# shield-rs422-B.net
KiCad netlist of a schematic drawn in EAGLE
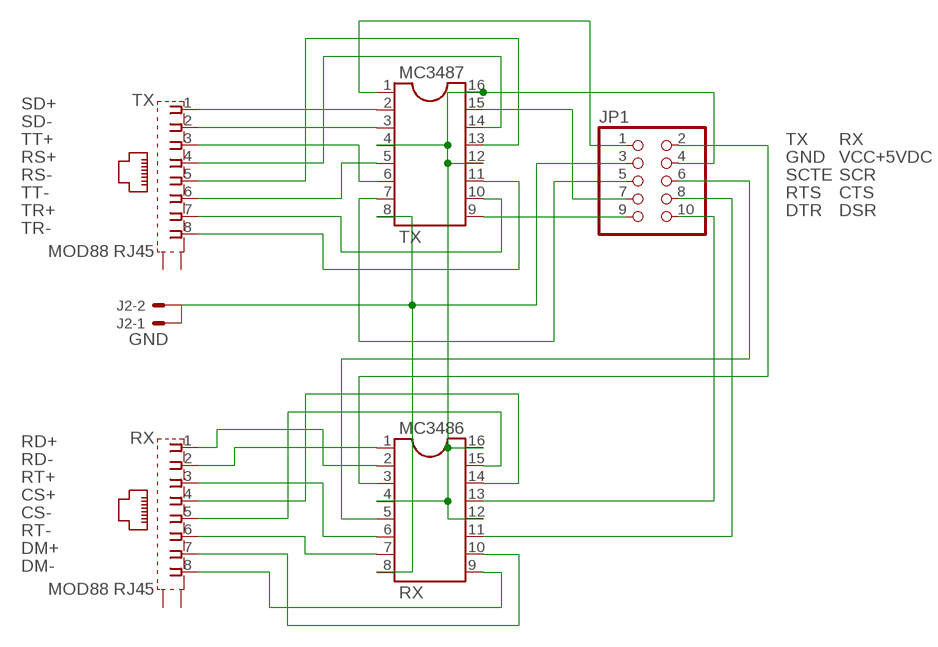
[diagram p0: schematic, sheet 1]

(export (version "E")
  (design (tool "Eeschema 10.0.6"))
  (components
    (comp (ref "J2")
      (value "GND")
      (footprint "eagle-import:7395-02")
      (libsource (lib "eagle-import") (part "22-?-0205-7028"))
    )
    (comp (ref "JP1")
      (value "PINHD-2X5/90")
      (footprint "eagle-import:2X05_90")
      (libsource (lib "eagle-import") (part "PINHD-2X5/90"))
    )
    (comp (ref "MC3486")
      (value "RX")
      (footprint "eagle-import:DIL16")
      (libsource (lib "eagle-import") (part "DIL16"))
    )
    (comp (ref "MC3487")
      (value "TX")
      (footprint "eagle-import:DIL16")
      (libsource (lib "eagle-import") (part "DIL16"))
    )
    (comp (ref "RX")
      (value "MOD88 RJ45")
      (footprint "eagle-import:GLX-S-88M")
      (libsource (lib "eagle-import") (part "GLX-S-88M"))
    )
    (comp (ref "TX")
      (value "MOD88 RJ45")
      (footprint "eagle-import:GLX-S-88M")
      (libsource (lib "eagle-import") (part "GLX-S-88M"))
    )
  )
  (nets
    (net (code "1") (name "/CS+") (class "Default")
      (node (ref "MC3486") (pin "14") (pinfunction "14_14") (pintype "passive"))
      (node (ref "RX") (pin "4") (pinfunction "4_4") (pintype "passive"))
    )
    (net (code "2") (name "/CS-") (class "Default")
      (node (ref "MC3486") (pin "15") (pinfunction "15_15") (pintype "passive"))
      (node (ref "RX") (pin "5") (pinfunction "5_5") (pintype "passive"))
    )
    (net (code "3") (name "/CTS") (class "Default")
      (node (ref "JP1") (pin "8") (pinfunction "8_8") (pintype "passive"))
      (node (ref "MC3486") (pin "11") (pinfunction "11_11") (pintype "passive"))
    )
    (net (code "4") (name "/DM+") (class "Default")
      (node (ref "MC3486") (pin "10") (pinfunction "10_10") (pintype "passive"))
      (node (ref "RX") (pin "7") (pinfunction "7_7") (pintype "passive"))
    )
    (net (code "5") (name "/DM-") (class "Default")
      (node (ref "MC3486") (pin "9") (pinfunction "9_9") (pintype "passive"))
      (node (ref "RX") (pin "8") (pinfunction "8_8") (pintype "passive"))
    )
    (net (code "6") (name "/DSR") (class "Default")
      (node (ref "JP1") (pin "10") (pinfunction "10_10") (pintype "passive"))
      (node (ref "MC3486") (pin "13") (pinfunction "13_13") (pintype "passive"))
    )
    (net (code "7") (name "/DTR") (class "Default")
      (node (ref "JP1") (pin "9") (pinfunction "9_9") (pintype "passive"))
      (node (ref "MC3487") (pin "9") (pinfunction "9_9") (pintype "passive"))
    )
    (net (code "8") (name "/GND") (class "Default")
      (node (ref "J2") (pin "1") (pinfunction "S_1") (pintype "passive"))
      (node (ref "J2") (pin "2") (pinfunction "S_2") (pintype "passive"))
      (node (ref "JP1") (pin "3") (pinfunction "3_3") (pintype "passive"))
      (node (ref "MC3486") (pin "8") (pinfunction "8_8") (pintype "passive"))
      (node (ref "MC3487") (pin "8") (pinfunction "8_8") (pintype "passive"))
    )
    (net (code "9") (name "/RD+") (class "Default")
      (node (ref "MC3486") (pin "2") (pinfunction "2_2") (pintype "passive"))
      (node (ref "RX") (pin "1") (pinfunction "1_1") (pintype "passive"))
    )
    (net (code "10") (name "/RD-") (class "Default")
      (node (ref "MC3486") (pin "1") (pinfunction "1_1") (pintype "passive"))
      (node (ref "RX") (pin "2") (pinfunction "2_2") (pintype "passive"))
    )
    (net (code "11") (name "/RS+") (class "Default")
      (node (ref "MC3487") (pin "14") (pinfunction "14_14") (pintype "passive"))
      (node (ref "TX") (pin "4") (pinfunction "4_4") (pintype "passive"))
    )
    (net (code "12") (name "/RS-") (class "Default")
      (node (ref "MC3487") (pin "13") (pinfunction "13_13") (pintype "passive"))
      (node (ref "TX") (pin "5") (pinfunction "5_5") (pintype "passive"))
    )
    (net (code "13") (name "/RT+") (class "Default")
      (node (ref "MC3486") (pin "6") (pinfunction "6_6") (pintype "passive"))
      (node (ref "RX") (pin "3") (pinfunction "3_3") (pintype "passive"))
    )
    (net (code "14") (name "/RT-") (class "Default")
      (node (ref "MC3486") (pin "7") (pinfunction "7_7") (pintype "passive"))
      (node (ref "RX") (pin "6") (pinfunction "6_6") (pintype "passive"))
    )
    (net (code "15") (name "/RTS") (class "Default")
      (node (ref "JP1") (pin "7") (pinfunction "7_7") (pintype "passive"))
      (node (ref "MC3487") (pin "15") (pinfunction "15_15") (pintype "passive"))
    )
    (net (code "16") (name "/RX") (class "Default")
      (node (ref "JP1") (pin "2") (pinfunction "2_2") (pintype "passive"))
      (node (ref "MC3486") (pin "3") (pinfunction "3_3") (pintype "passive"))
    )
    (net (code "17") (name "/SCR") (class "Default")
      (node (ref "JP1") (pin "6") (pinfunction "6_6") (pintype "passive"))
      (node (ref "MC3486") (pin "5") (pinfunction "5_5") (pintype "passive"))
    )
    (net (code "18") (name "/SCTE") (class "Default")
      (node (ref "JP1") (pin "5") (pinfunction "5_5") (pintype "passive"))
      (node (ref "MC3487") (pin "7") (pinfunction "7_7") (pintype "passive"))
    )
    (net (code "19") (name "/SD+") (class "Default")
      (node (ref "MC3487") (pin "2") (pinfunction "2_2") (pintype "passive"))
      (node (ref "TX") (pin "1") (pinfunction "1_1") (pintype "passive"))
    )
    (net (code "20") (name "/SD-") (class "Default")
      (node (ref "MC3487") (pin "3") (pinfunction "3_3") (pintype "passive"))
      (node (ref "TX") (pin "2") (pinfunction "2_2") (pintype "passive"))
    )
    (net (code "21") (name "/TR+") (class "Default")
      (node (ref "MC3487") (pin "10") (pinfunction "10_10") (pintype "passive"))
      (node (ref "TX") (pin "7") (pinfunction "7_7") (pintype "passive"))
    )
    (net (code "22") (name "/TR-") (class "Default")
      (node (ref "MC3487") (pin "11") (pinfunction "11_11") (pintype "passive"))
      (node (ref "TX") (pin "8") (pinfunction "8_8") (pintype "passive"))
    )
    (net (code "23") (name "/TT+") (class "Default")
      (node (ref "MC3487") (pin "6") (pinfunction "6_6") (pintype "passive"))
      (node (ref "TX") (pin "3") (pinfunction "3_3") (pintype "passive"))
    )
    (net (code "24") (name "/TT-") (class "Default")
      (node (ref "MC3487") (pin "5") (pinfunction "5_5") (pintype "passive"))
      (node (ref "TX") (pin "6") (pinfunction "6_6") (pintype "passive"))
    )
    (net (code "25") (name "/TX") (class "Default")
      (node (ref "JP1") (pin "1") (pinfunction "1_1") (pintype "passive"))
      (node (ref "MC3487") (pin "1") (pinfunction "1_1") (pintype "passive"))
    )
    (net (code "26") (name "/VCC+5VDC") (class "Default")
      (node (ref "JP1") (pin "4") (pinfunction "4_4") (pintype "passive"))
      (node (ref "MC3486") (pin "12") (pinfunction "12_12") (pintype "passive"))
      (node (ref "MC3486") (pin "16") (pinfunction "16_16") (pintype "passive"))
      (node (ref "MC3486") (pin "4") (pinfunction "4_4") (pintype "passive"))
      (node (ref "MC3487") (pin "12") (pinfunction "12_12") (pintype "passive"))
      (node (ref "MC3487") (pin "16") (pinfunction "16_16") (pintype "passive"))
      (node (ref "MC3487") (pin "4") (pinfunction "4_4") (pintype "passive"))
    )
    (net (code "27") (name "unconnected-(RX-PadS1)") (class "Default")
      (node (ref "RX") (pin "S1") (pinfunction "S1_S1") (pintype "passive"))
    )
    (net (code "28") (name "unconnected-(RX-PadS2)") (class "Default")
      (node (ref "RX") (pin "S2") (pinfunction "S2_S2") (pintype "passive"))
    )
    (net (code "29") (name "unconnected-(TX-PadS1)") (class "Default")
      (node (ref "TX") (pin "S1") (pinfunction "S1_S1") (pintype "passive"))
    )
    (net (code "30") (name "unconnected-(TX-PadS2)") (class "Default")
      (node (ref "TX") (pin "S2") (pinfunction "S2_S2") (pintype "passive"))
    )
  )
)
